# Sheet2.net
KiCad netlist of a schematic drawn in Altium Designer
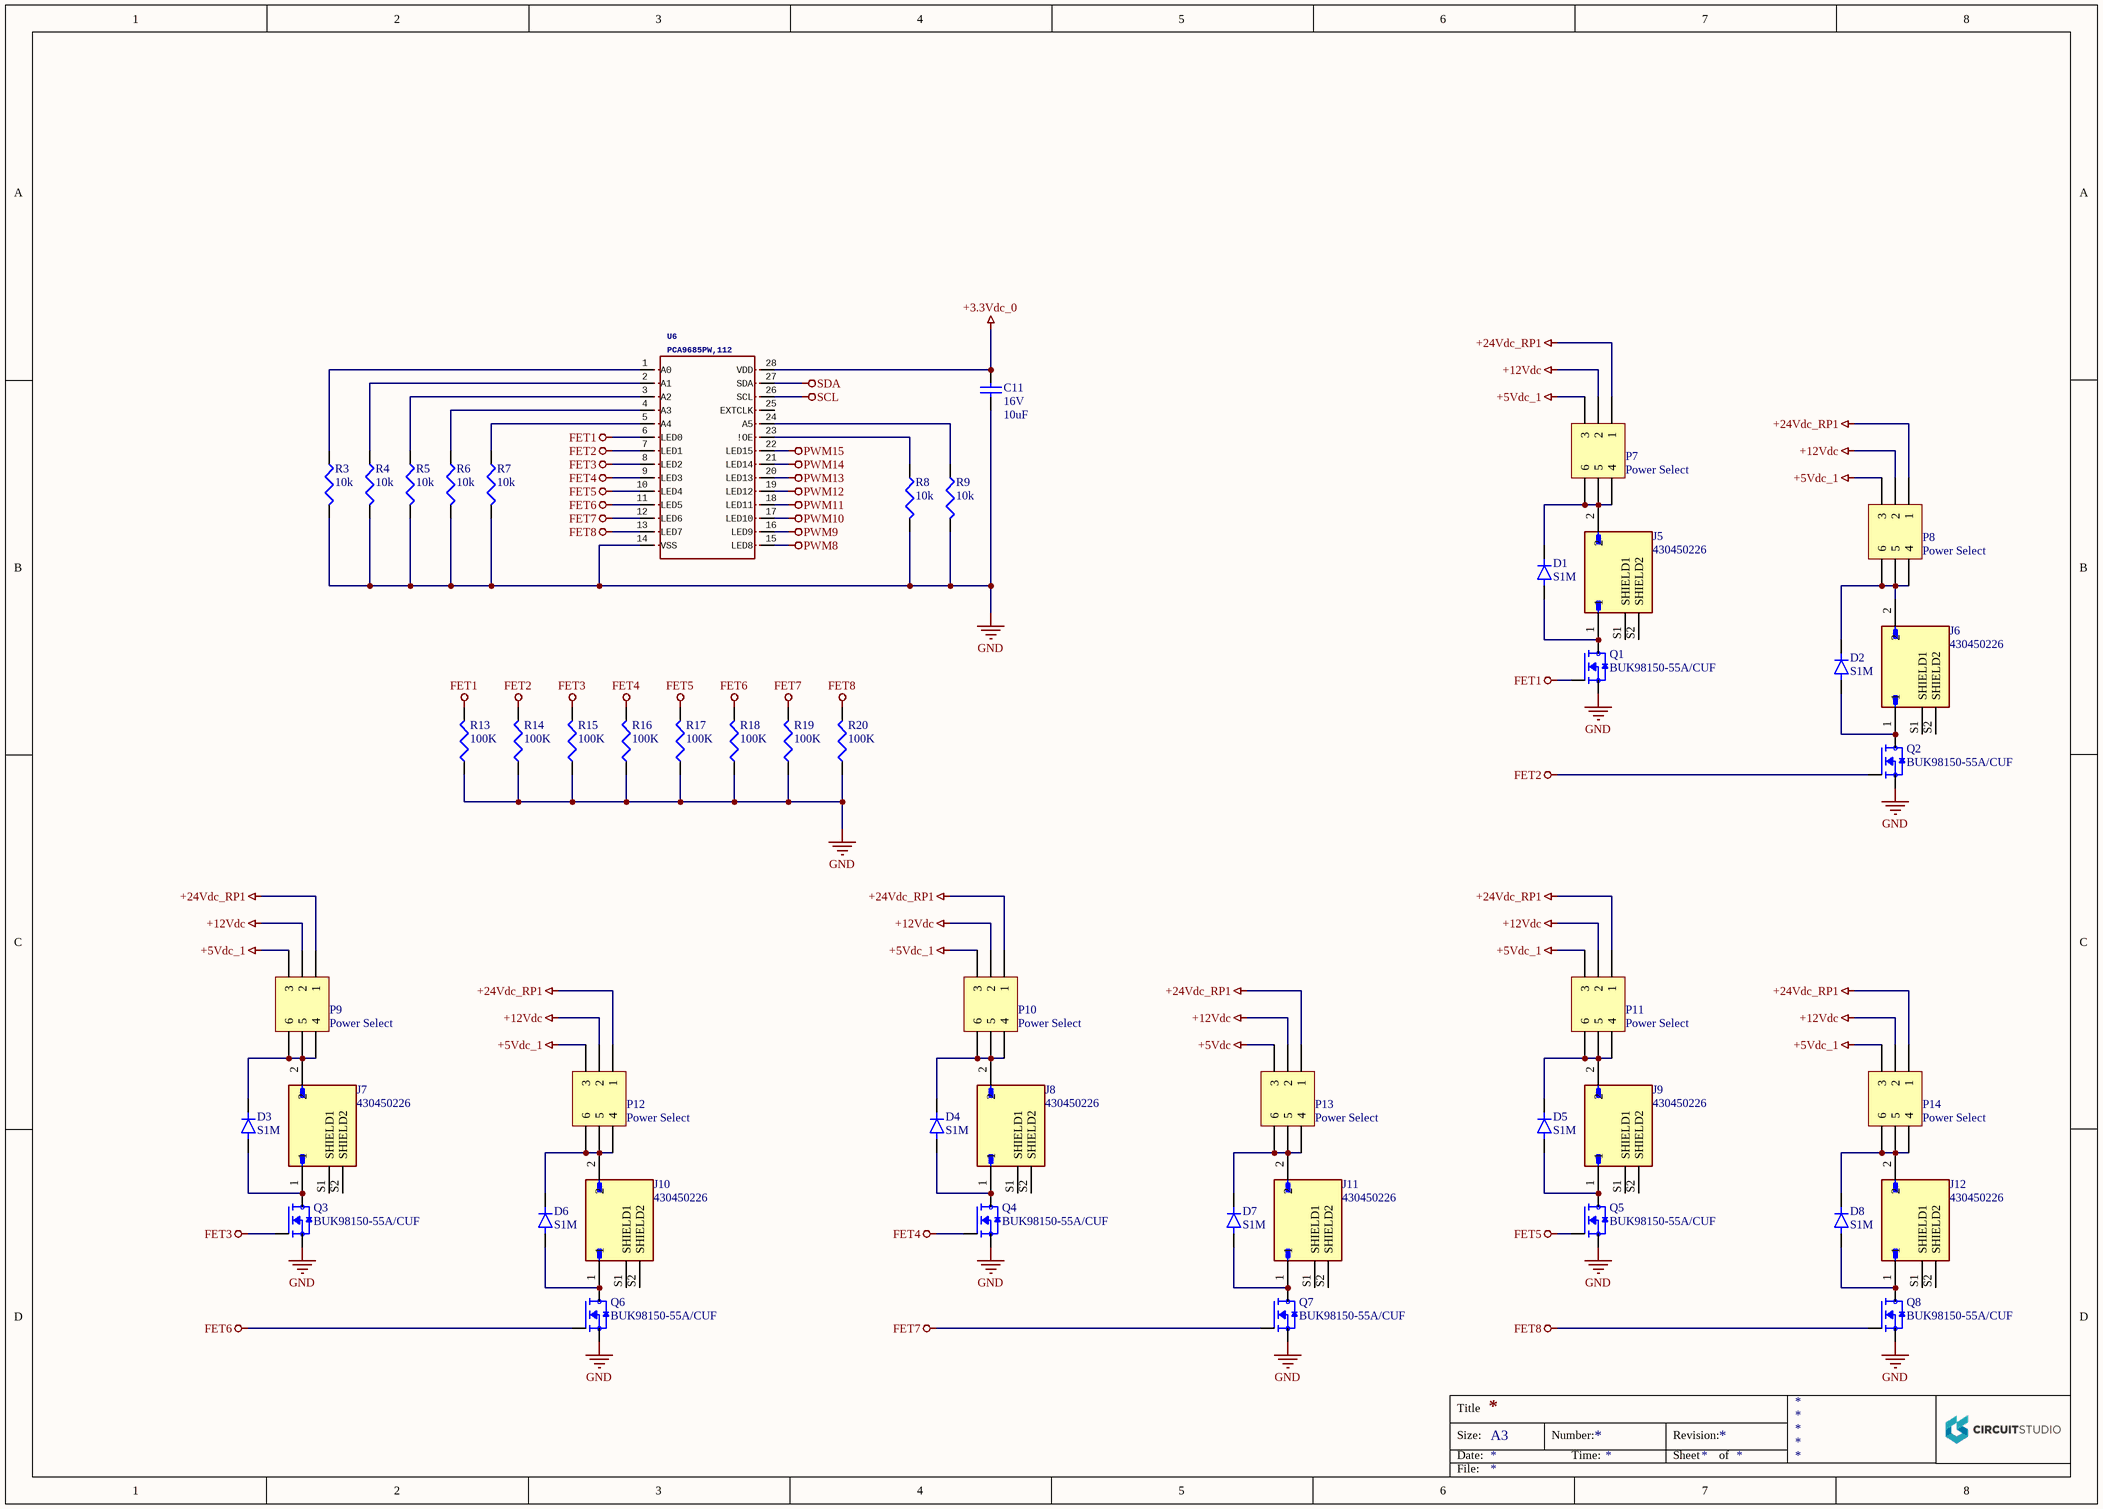
[diagram p0: Sheet2.SchDoc]

(export (version "E")
  (design (tool "Eeschema 10.0.6"))
  (components
    (comp (ref "C11")
      (value "16V")
      (footprint "1608[0603]")
      (description "CAP CER 10UF 16V X5R 0603")
      (fields
        (field (name "ALTIUM_VALUE") "10uF")
        (field (name "MANUFACTURER PART #") "CC0603KRX5R7BB106")
        (field (name "MANUFACTURER") "YAGEO")
      )
      (libsource (lib "Miscellaneous Devices") (part "Cap Semi"))
    )
    (comp (ref "D1")
      (value "S1M")
      (footprint "DIOM4325X250N")
      (description "DIODE GEN PURP 1KV 1A SMA")
      (fields
        (field (name "MANUFACTURER PART #") "S1MLHRVG")
        (field (name "MANUFACTURER") "Taiwan Semiconductor")
      )
      (libsource (lib "S1M") (part "S1M"))
    )
    (comp (ref "D2")
      (value "S1M")
      (footprint "DIOM4325X250N")
      (description "DIODE GEN PURP 1KV 1A SMA")
      (fields
        (field (name "MANUFACTURER PART #") "S1MLHRVG")
        (field (name "MANUFACTURER") "Taiwan Semiconductor")
      )
      (libsource (lib "S1M") (part "S1M"))
    )
    (comp (ref "D3")
      (value "S1M")
      (footprint "DIOM4325X250N")
      (description "DIODE GEN PURP 1KV 1A SMA")
      (fields
        (field (name "MANUFACTURER PART #") "S1MLHRVG")
        (field (name "MANUFACTURER") "Taiwan Semiconductor")
      )
      (libsource (lib "S1M") (part "S1M"))
    )
    (comp (ref "D4")
      (value "S1M")
      (footprint "DIOM4325X250N")
      (description "DIODE GEN PURP 1KV 1A SMA")
      (fields
        (field (name "MANUFACTURER PART #") "S1MLHRVG")
        (field (name "MANUFACTURER") "Taiwan Semiconductor")
      )
      (libsource (lib "S1M") (part "S1M"))
    )
    (comp (ref "D5")
      (value "S1M")
      (footprint "DIOM4325X250N")
      (description "DIODE GEN PURP 1KV 1A SMA")
      (fields
        (field (name "MANUFACTURER PART #") "S1MLHRVG")
        (field (name "MANUFACTURER") "Taiwan Semiconductor")
      )
      (libsource (lib "S1M") (part "S1M"))
    )
    (comp (ref "D6")
      (value "S1M")
      (footprint "DIOM4325X250N")
      (description "DIODE GEN PURP 1KV 1A SMA")
      (fields
        (field (name "MANUFACTURER PART #") "S1MLHRVG")
        (field (name "MANUFACTURER") "Taiwan Semiconductor")
      )
      (libsource (lib "S1M") (part "S1M"))
    )
    (comp (ref "D7")
      (value "S1M")
      (footprint "DIOM4325X250N")
      (description "DIODE GEN PURP 1KV 1A SMA")
      (fields
        (field (name "MANUFACTURER PART #") "S1MLHRVG")
        (field (name "MANUFACTURER") "Taiwan Semiconductor")
      )
      (libsource (lib "S1M") (part "S1M"))
    )
    (comp (ref "D8")
      (value "S1M")
      (footprint "DIOM4325X250N")
      (description "DIODE GEN PURP 1KV 1A SMA")
      (fields
        (field (name "MANUFACTURER PART #") "S1MLHRVG")
        (field (name "MANUFACTURER") "Taiwan Semiconductor")
      )
      (libsource (lib "S1M") (part "S1M"))
    )
    (comp (ref "J5")
      (value "430450226")
      (footprint "MOLEX_430450226")
      (description "CONN HEADER VERT 2POS")
      (fields (field (name "MANUFACTURER PART #") "0430450226"))
      (libsource (lib "2P_Vert_Microfit") (part "430450226"))
    )
    (comp (ref "J6")
      (value "430450226")
      (footprint "MOLEX_430450226")
      (description "CONN HEADER VERT 2POS")
      (fields (field (name "MANUFACTURER PART #") "0430450226"))
      (libsource (lib "2P_Vert_Microfit") (part "430450226"))
    )
    (comp (ref "J7")
      (value "430450226")
      (footprint "MOLEX_430450226")
      (description "CONN HEADER VERT 2POS")
      (fields (field (name "MANUFACTURER PART #") "0430450226"))
      (libsource (lib "2P_Vert_Microfit") (part "430450226"))
    )
    (comp (ref "J8")
      (value "430450226")
      (footprint "MOLEX_430450226")
      (description "CONN HEADER VERT 2POS")
      (fields (field (name "MANUFACTURER PART #") "0430450226"))
      (libsource (lib "2P_Vert_Microfit") (part "430450226"))
    )
    (comp (ref "J9")
      (value "430450226")
      (footprint "MOLEX_430450226")
      (description "CONN HEADER VERT 2POS")
      (fields (field (name "MANUFACTURER PART #") "0430450226"))
      (libsource (lib "2P_Vert_Microfit") (part "430450226"))
    )
    (comp (ref "J10")
      (value "430450226")
      (footprint "MOLEX_430450226")
      (description "CONN HEADER VERT 2POS")
      (fields (field (name "MANUFACTURER PART #") "0430450226"))
      (libsource (lib "2P_Vert_Microfit") (part "430450226"))
    )
    (comp (ref "J11")
      (value "430450226")
      (footprint "MOLEX_430450226")
      (description "CONN HEADER VERT 2POS")
      (fields (field (name "MANUFACTURER PART #") "0430450226"))
      (libsource (lib "2P_Vert_Microfit") (part "430450226"))
    )
    (comp (ref "J12")
      (value "430450226")
      (footprint "MOLEX_430450226")
      (description "CONN HEADER VERT 2POS")
      (fields (field (name "MANUFACTURER PART #") "0430450226"))
      (libsource (lib "2P_Vert_Microfit") (part "430450226"))
    )
    (comp (ref "P7")
      (value "Power Select")
      (footprint "HDR2X3_CEN")
      (description "Header, 3-Pin, Dual row")
      (fields
        (field (name "MANUFACTURER PART #") "67997-206HLF")
        (field (name "MANUFACTURER") "Amphenol ICC (FCI)")
      )
      (libsource (lib "Miscellaneous Connectors") (part "Header 3X2A"))
    )
    (comp (ref "P8")
      (value "Power Select")
      (footprint "HDR2X3_CEN")
      (description "Header, 3-Pin, Dual row")
      (fields
        (field (name "MANUFACTURER PART #") "67997-206HLF")
        (field (name "MANUFACTURER") "Amphenol ICC (FCI)")
      )
      (libsource (lib "Miscellaneous Connectors") (part "Header 3X2A"))
    )
    (comp (ref "P9")
      (value "Power Select")
      (footprint "HDR2X3_CEN")
      (description "Header, 3-Pin, Dual row")
      (fields
        (field (name "MANUFACTURER PART #") "67997-206HLF")
        (field (name "MANUFACTURER") "Amphenol ICC (FCI)")
      )
      (libsource (lib "Miscellaneous Connectors") (part "Header 3X2A"))
    )
    (comp (ref "P10")
      (value "Power Select")
      (footprint "HDR2X3_CEN")
      (description "Header, 3-Pin, Dual row")
      (fields
        (field (name "MANUFACTURER PART #") "67997-206HLF")
        (field (name "MANUFACTURER") "Amphenol ICC (FCI)")
      )
      (libsource (lib "Miscellaneous Connectors") (part "Header 3X2A"))
    )
    (comp (ref "P11")
      (value "Power Select")
      (footprint "HDR2X3_CEN")
      (description "Header, 3-Pin, Dual row")
      (fields
        (field (name "MANUFACTURER PART #") "67997-206HLF")
        (field (name "MANUFACTURER") "Amphenol ICC (FCI)")
      )
      (libsource (lib "Miscellaneous Connectors") (part "Header 3X2A"))
    )
    (comp (ref "P12")
      (value "Power Select")
      (footprint "HDR2X3_CEN")
      (description "Header, 3-Pin, Dual row")
      (fields
        (field (name "MANUFACTURER PART #") "67997-206HLF")
        (field (name "MANUFACTURER") "Amphenol ICC (FCI)")
      )
      (libsource (lib "Miscellaneous Connectors") (part "Header 3X2A"))
    )
    (comp (ref "P13")
      (value "Power Select")
      (footprint "HDR2X3_CEN")
      (description "Header, 3-Pin, Dual row")
      (fields
        (field (name "MANUFACTURER PART #") "67997-206HLF")
        (field (name "MANUFACTURER") "Amphenol ICC (FCI)")
      )
      (libsource (lib "Miscellaneous Connectors") (part "Header 3X2A"))
    )
    (comp (ref "P14")
      (value "Power Select")
      (footprint "HDR2X3_CEN")
      (description "Header, 3-Pin, Dual row")
      (fields
        (field (name "MANUFACTURER PART #") "67997-206HLF")
        (field (name "MANUFACTURER") "Amphenol ICC (FCI)")
      )
      (libsource (lib "Miscellaneous Connectors") (part "Header 3X2A"))
    )
    (comp (ref "Q1")
      (value "BUK98150-55A/CUF")
      (footprint "SOT230P700X180-4N")
      (description "N-MOSFET N-CH 55V 5.5A SOT223")
      (fields (field (name "MANUFACTURER") "Nexperia USA"))
      (libsource (lib "BUK98150-55A_CUF") (part "BUK98150-55A/CUF"))
    )
    (comp (ref "Q2")
      (value "BUK98150-55A/CUF")
      (footprint "SOT230P700X180-4N")
      (description "N-MOSFET N-CH 55V 5.5A SOT223")
      (fields (field (name "MANUFACTURER") "Nexperia USA"))
      (libsource (lib "BUK98150-55A_CUF") (part "BUK98150-55A/CUF"))
    )
    (comp (ref "Q3")
      (value "BUK98150-55A/CUF")
      (footprint "SOT230P700X180-4N")
      (description "N-MOSFET N-CH 55V 5.5A SOT223")
      (fields (field (name "MANUFACTURER") "Nexperia USA"))
      (libsource (lib "BUK98150-55A_CUF") (part "BUK98150-55A/CUF"))
    )
    (comp (ref "Q4")
      (value "BUK98150-55A/CUF")
      (footprint "SOT230P700X180-4N")
      (description "N-MOSFET N-CH 55V 5.5A SOT223")
      (fields (field (name "MANUFACTURER") "Nexperia USA"))
      (libsource (lib "BUK98150-55A_CUF") (part "BUK98150-55A/CUF"))
    )
    (comp (ref "Q5")
      (value "BUK98150-55A/CUF")
      (footprint "SOT230P700X180-4N")
      (description "N-MOSFET N-CH 55V 5.5A SOT223")
      (fields (field (name "MANUFACTURER") "Nexperia USA"))
      (libsource (lib "BUK98150-55A_CUF") (part "BUK98150-55A/CUF"))
    )
    (comp (ref "Q6")
      (value "BUK98150-55A/CUF")
      (footprint "SOT230P700X180-4N")
      (description "N-MOSFET N-CH 55V 5.5A SOT223")
      (fields (field (name "MANUFACTURER") "Nexperia USA"))
      (libsource (lib "BUK98150-55A_CUF") (part "BUK98150-55A/CUF"))
    )
    (comp (ref "Q7")
      (value "BUK98150-55A/CUF")
      (footprint "SOT230P700X180-4N")
      (description "N-MOSFET N-CH 55V 5.5A SOT223")
      (fields (field (name "MANUFACTURER") "Nexperia USA"))
      (libsource (lib "BUK98150-55A_CUF") (part "BUK98150-55A/CUF"))
    )
    (comp (ref "Q8")
      (value "BUK98150-55A/CUF")
      (footprint "SOT230P700X180-4N")
      (description "N-MOSFET N-CH 55V 5.5A SOT223")
      (fields (field (name "MANUFACTURER") "Nexperia USA"))
      (libsource (lib "BUK98150-55A_CUF") (part "BUK98150-55A/CUF"))
    )
    (comp (ref "R3")
      (value "10k")
      (footprint "0402")
      (description "RES 10 KOHM 1% 1/8W 0402")
      (fields (field (name "MANUFACTURER PART #") "AC0402FR-7W10KL") (field (name "MANUFACTURER") "YAGEO"))
      (libsource (lib "Miscellaneous Devices") (part "Res3"))
    )
    (comp (ref "R4")
      (value "10k")
      (footprint "0402")
      (description "RES 10 KOHM 1% 1/8W 0402")
      (fields (field (name "MANUFACTURER PART #") "AC0402FR-7W10KL") (field (name "MANUFACTURER") "YAGEO"))
      (libsource (lib "Miscellaneous Devices") (part "Res3"))
    )
    (comp (ref "R5")
      (value "10k")
      (footprint "0402")
      (description "RES 10 KOHM 1% 1/8W 0402")
      (fields (field (name "MANUFACTURER PART #") "AC0402FR-7W10KL") (field (name "MANUFACTURER") "YAGEO"))
      (libsource (lib "Miscellaneous Devices") (part "Res3"))
    )
    (comp (ref "R6")
      (value "10k")
      (footprint "0402")
      (description "RES 10 KOHM 1% 1/8W 0402")
      (fields (field (name "MANUFACTURER PART #") "AC0402FR-7W10KL") (field (name "MANUFACTURER") "YAGEO"))
      (libsource (lib "Miscellaneous Devices") (part "Res3"))
    )
    (comp (ref "R7")
      (value "10k")
      (footprint "0402")
      (description "RES 10 KOHM 1% 1/8W 0402")
      (fields (field (name "MANUFACTURER PART #") "AC0402FR-7W10KL") (field (name "MANUFACTURER") "YAGEO"))
      (libsource (lib "Miscellaneous Devices") (part "Res3"))
    )
    (comp (ref "R8")
      (value "10k")
      (footprint "0402")
      (description "RES 10 KOHM 1% 1/8W 0402")
      (fields (field (name "MANUFACTURER PART #") "AC0402FR-7W10KL") (field (name "MANUFACTURER") "YAGEO"))
      (libsource (lib "Miscellaneous Devices") (part "Res3"))
    )
    (comp (ref "R9")
      (value "10k")
      (footprint "0402")
      (description "RES 10 KOHM 1% 1/8W 0402")
      (fields (field (name "MANUFACTURER PART #") "AC0402FR-7W10KL") (field (name "MANUFACTURER") "YAGEO"))
      (libsource (lib "Miscellaneous Devices") (part "Res3"))
    )
    (comp (ref "R13")
      (value "100K")
      (footprint "J1-0603")
      (description "RES 100K OHM 1% 1/4W 0603")
      (fields (field (name "MANUFACTURER PART #") "SR0603FR-7T100KL") (field (name "MANUFACTURER") "YAGEO"))
      (libsource (lib "Miscellaneous Devices") (part "Res3"))
    )
    (comp (ref "R14")
      (value "100K")
      (footprint "J1-0603")
      (description "RES 100K OHM 1% 1/4W 0603")
      (fields (field (name "MANUFACTURER PART #") "SR0603FR-7T100KL") (field (name "MANUFACTURER") "YAGEO"))
      (libsource (lib "Miscellaneous Devices") (part "Res3"))
    )
    (comp (ref "R15")
      (value "100K")
      (footprint "J1-0603")
      (description "RES 100K OHM 1% 1/4W 0603")
      (fields (field (name "MANUFACTURER PART #") "SR0603FR-7T100KL") (field (name "MANUFACTURER") "YAGEO"))
      (libsource (lib "Miscellaneous Devices") (part "Res3"))
    )
    (comp (ref "R16")
      (value "100K")
      (footprint "J1-0603")
      (description "RES 100K OHM 1% 1/4W 0603")
      (fields (field (name "MANUFACTURER PART #") "SR0603FR-7T100KL") (field (name "MANUFACTURER") "YAGEO"))
      (libsource (lib "Miscellaneous Devices") (part "Res3"))
    )
    (comp (ref "R17")
      (value "100K")
      (footprint "J1-0603")
      (description "RES 100K OHM 1% 1/4W 0603")
      (fields (field (name "MANUFACTURER PART #") "SR0603FR-7T100KL") (field (name "MANUFACTURER") "YAGEO"))
      (libsource (lib "Miscellaneous Devices") (part "Res3"))
    )
    (comp (ref "R18")
      (value "100K")
      (footprint "J1-0603")
      (description "RES 100K OHM 1% 1/4W 0603")
      (fields (field (name "MANUFACTURER PART #") "SR0603FR-7T100KL") (field (name "MANUFACTURER") "YAGEO"))
      (libsource (lib "Miscellaneous Devices") (part "Res3"))
    )
    (comp (ref "R19")
      (value "100K")
      (footprint "J1-0603")
      (description "RES 100K OHM 1% 1/4W 0603")
      (fields (field (name "MANUFACTURER PART #") "SR0603FR-7T100KL") (field (name "MANUFACTURER") "YAGEO"))
      (libsource (lib "Miscellaneous Devices") (part "Res3"))
    )
    (comp (ref "R20")
      (value "100K")
      (footprint "J1-0603")
      (description "RES 100K OHM 1% 1/4W 0603")
      (fields (field (name "MANUFACTURER PART #") "SR0603FR-7T100KL") (field (name "MANUFACTURER") "YAGEO"))
      (libsource (lib "Miscellaneous Devices") (part "Res3"))
    )
    (comp (ref "U6")
      (value "PCA9685PW,112")
      (footprint "TSSOP28-0.65-9.7X4.4MM")
      (fields (field (name "MANUFACTURER") "NXP USA"))
      (libsource (lib "PCA9685PW") (part "DRIVER-PCA9685PW(TSSOP28)"))
    )
  )
  (nets
    (net (code "1") (name "+3.3Vdc_0") (class "Default")
      (node (ref "C11") (pin "1") (pinfunction "1_1") (pintype "passive"))
      (node (ref "U6") (pin "28") (pinfunction "VDD_28") (pintype "passive"))
    )
    (net (code "2") (name "+5Vdc") (class "Default")
      (node (ref "P13") (pin "3") (pinfunction "3_3") (pintype "passive"))
    )
    (net (code "3") (name "+5Vdc_1") (class "Default")
      (node (ref "P10") (pin "3") (pinfunction "3_3") (pintype "passive"))
      (node (ref "P11") (pin "3") (pinfunction "3_3") (pintype "passive"))
      (node (ref "P12") (pin "3") (pinfunction "3_3") (pintype "passive"))
      (node (ref "P14") (pin "3") (pinfunction "3_3") (pintype "passive"))
      (node (ref "P7") (pin "3") (pinfunction "3_3") (pintype "passive"))
      (node (ref "P8") (pin "3") (pinfunction "3_3") (pintype "passive"))
      (node (ref "P9") (pin "3") (pinfunction "3_3") (pintype "passive"))
    )
    (net (code "4") (name "+12Vdc") (class "Default")
      (node (ref "P10") (pin "2") (pinfunction "2_2") (pintype "passive"))
      (node (ref "P11") (pin "2") (pinfunction "2_2") (pintype "passive"))
      (node (ref "P12") (pin "2") (pinfunction "2_2") (pintype "passive"))
      (node (ref "P13") (pin "2") (pinfunction "2_2") (pintype "passive"))
      (node (ref "P14") (pin "2") (pinfunction "2_2") (pintype "passive"))
      (node (ref "P7") (pin "2") (pinfunction "2_2") (pintype "passive"))
      (node (ref "P8") (pin "2") (pinfunction "2_2") (pintype "passive"))
      (node (ref "P9") (pin "2") (pinfunction "2_2") (pintype "passive"))
    )
    (net (code "5") (name "+24Vdc_RP1") (class "Default")
      (node (ref "P10") (pin "1") (pinfunction "1_1") (pintype "passive"))
      (node (ref "P11") (pin "1") (pinfunction "1_1") (pintype "passive"))
      (node (ref "P12") (pin "1") (pinfunction "1_1") (pintype "passive"))
      (node (ref "P13") (pin "1") (pinfunction "1_1") (pintype "passive"))
      (node (ref "P14") (pin "1") (pinfunction "1_1") (pintype "passive"))
      (node (ref "P7") (pin "1") (pinfunction "1_1") (pintype "passive"))
      (node (ref "P8") (pin "1") (pinfunction "1_1") (pintype "passive"))
      (node (ref "P9") (pin "1") (pinfunction "1_1") (pintype "passive"))
    )
    (net (code "6") (name "FET1") (class "Default")
      (node (ref "Q1") (pin "1") (pinfunction "G_1") (pintype "passive"))
      (node (ref "R13") (pin "2") (pinfunction "2_2") (pintype "passive"))
      (node (ref "U6") (pin "6") (pinfunction "LED0_6") (pintype "passive"))
    )
    (net (code "7") (name "FET2") (class "Default")
      (node (ref "Q2") (pin "1") (pinfunction "G_1") (pintype "passive"))
      (node (ref "R14") (pin "2") (pinfunction "2_2") (pintype "passive"))
      (node (ref "U6") (pin "7") (pinfunction "LED1_7") (pintype "passive"))
    )
    (net (code "8") (name "FET3") (class "Default")
      (node (ref "Q3") (pin "1") (pinfunction "G_1") (pintype "passive"))
      (node (ref "R15") (pin "2") (pinfunction "2_2") (pintype "passive"))
      (node (ref "U6") (pin "8") (pinfunction "LED2_8") (pintype "passive"))
    )
    (net (code "9") (name "FET4") (class "Default")
      (node (ref "Q4") (pin "1") (pinfunction "G_1") (pintype "passive"))
      (node (ref "R16") (pin "2") (pinfunction "2_2") (pintype "passive"))
      (node (ref "U6") (pin "9") (pinfunction "LED3_9") (pintype "passive"))
    )
    (net (code "10") (name "FET5") (class "Default")
      (node (ref "Q5") (pin "1") (pinfunction "G_1") (pintype "passive"))
      (node (ref "R17") (pin "2") (pinfunction "2_2") (pintype "passive"))
      (node (ref "U6") (pin "10") (pinfunction "LED4_10") (pintype "passive"))
    )
    (net (code "11") (name "FET6") (class "Default")
      (node (ref "Q6") (pin "1") (pinfunction "G_1") (pintype "passive"))
      (node (ref "R18") (pin "2") (pinfunction "2_2") (pintype "passive"))
      (node (ref "U6") (pin "11") (pinfunction "LED5_11") (pintype "passive"))
    )
    (net (code "12") (name "FET7") (class "Default")
      (node (ref "Q7") (pin "1") (pinfunction "G_1") (pintype "passive"))
      (node (ref "R19") (pin "2") (pinfunction "2_2") (pintype "passive"))
      (node (ref "U6") (pin "12") (pinfunction "LED6_12") (pintype "passive"))
    )
    (net (code "13") (name "FET8") (class "Default")
      (node (ref "Q8") (pin "1") (pinfunction "G_1") (pintype "passive"))
      (node (ref "R20") (pin "2") (pinfunction "2_2") (pintype "passive"))
      (node (ref "U6") (pin "13") (pinfunction "LED7_13") (pintype "passive"))
    )
    (net (code "14") (name "GND") (class "Default")
      (node (ref "C11") (pin "2") (pinfunction "2_2") (pintype "passive"))
      (node (ref "Q1") (pin "3") (pinfunction "S_3") (pintype "passive"))
      (node (ref "Q2") (pin "3") (pinfunction "S_3") (pintype "passive"))
      (node (ref "Q3") (pin "3") (pinfunction "S_3") (pintype "passive"))
      (node (ref "Q4") (pin "3") (pinfunction "S_3") (pintype "passive"))
      (node (ref "Q5") (pin "3") (pinfunction "S_3") (pintype "passive"))
      (node (ref "Q6") (pin "3") (pinfunction "S_3") (pintype "passive"))
      (node (ref "Q7") (pin "3") (pinfunction "S_3") (pintype "passive"))
      (node (ref "Q8") (pin "3") (pinfunction "S_3") (pintype "passive"))
      (node (ref "R13") (pin "1") (pinfunction "1_1") (pintype "passive"))
      (node (ref "R14") (pin "1") (pinfunction "1_1") (pintype "passive"))
      (node (ref "R15") (pin "1") (pinfunction "1_1") (pintype "passive"))
      (node (ref "R16") (pin "1") (pinfunction "1_1") (pintype "passive"))
      (node (ref "R17") (pin "1") (pinfunction "1_1") (pintype "passive"))
      (node (ref "R18") (pin "1") (pinfunction "1_1") (pintype "passive"))
      (node (ref "R19") (pin "1") (pinfunction "1_1") (pintype "passive"))
      (node (ref "R20") (pin "1") (pinfunction "1_1") (pintype "passive"))
      (node (ref "R3") (pin "2") (pinfunction "2_2") (pintype "passive"))
      (node (ref "R4") (pin "2") (pinfunction "2_2") (pintype "passive"))
      (node (ref "R5") (pin "2") (pinfunction "2_2") (pintype "passive"))
      (node (ref "R6") (pin "2") (pinfunction "2_2") (pintype "passive"))
      (node (ref "R7") (pin "2") (pinfunction "2_2") (pintype "passive"))
      (node (ref "R8") (pin "2") (pinfunction "2_2") (pintype "passive"))
      (node (ref "R9") (pin "2") (pinfunction "2_2") (pintype "passive"))
      (node (ref "U6") (pin "14") (pinfunction "VSS_14") (pintype "passive"))
    )
    (net (code "15") (name "Net-(D1-K)") (class "Default")
      (node (ref "D1") (pin "C") (pinfunction "K_C") (pintype "passive"))
      (node (ref "J5") (pin "2") (pinfunction "2_2") (pintype "passive"))
      (node (ref "P7") (pin "4") (pinfunction "4_4") (pintype "passive"))
      (node (ref "P7") (pin "5") (pinfunction "5_5") (pintype "passive"))
      (node (ref "P7") (pin "6") (pinfunction "6_6") (pintype "passive"))
    )
    (net (code "16") (name "Net-(D1-PadA)") (class "Default")
      (node (ref "D1") (pin "A") (pinfunction "A_A") (pintype "passive"))
      (node (ref "J5") (pin "1") (pinfunction "1_1") (pintype "passive"))
      (node (ref "Q1") (pin "2") (pinfunction "D_2") (pintype "passive"))
      (node (ref "Q1") (pin "4") (pinfunction "D_4") (pintype "passive"))
    )
    (net (code "17") (name "Net-(D2-K)") (class "Default")
      (node (ref "D2") (pin "C") (pinfunction "K_C") (pintype "passive"))
      (node (ref "J6") (pin "2") (pinfunction "2_2") (pintype "passive"))
      (node (ref "P8") (pin "4") (pinfunction "4_4") (pintype "passive"))
      (node (ref "P8") (pin "5") (pinfunction "5_5") (pintype "passive"))
      (node (ref "P8") (pin "6") (pinfunction "6_6") (pintype "passive"))
    )
    (net (code "18") (name "Net-(D2-PadA)") (class "Default")
      (node (ref "D2") (pin "A") (pinfunction "A_A") (pintype "passive"))
      (node (ref "J6") (pin "1") (pinfunction "1_1") (pintype "passive"))
      (node (ref "Q2") (pin "2") (pinfunction "D_2") (pintype "passive"))
      (node (ref "Q2") (pin "4") (pinfunction "D_4") (pintype "passive"))
    )
    (net (code "19") (name "Net-(D3-K)") (class "Default")
      (node (ref "D3") (pin "C") (pinfunction "K_C") (pintype "passive"))
      (node (ref "J7") (pin "2") (pinfunction "2_2") (pintype "passive"))
      (node (ref "P9") (pin "4") (pinfunction "4_4") (pintype "passive"))
      (node (ref "P9") (pin "5") (pinfunction "5_5") (pintype "passive"))
      (node (ref "P9") (pin "6") (pinfunction "6_6") (pintype "passive"))
    )
    (net (code "20") (name "Net-(D3-PadA)") (class "Default")
      (node (ref "D3") (pin "A") (pinfunction "A_A") (pintype "passive"))
      (node (ref "J7") (pin "1") (pinfunction "1_1") (pintype "passive"))
      (node (ref "Q3") (pin "2") (pinfunction "D_2") (pintype "passive"))
      (node (ref "Q3") (pin "4") (pinfunction "D_4") (pintype "passive"))
    )
    (net (code "21") (name "Net-(D4-K)") (class "Default")
      (node (ref "D4") (pin "C") (pinfunction "K_C") (pintype "passive"))
      (node (ref "J8") (pin "2") (pinfunction "2_2") (pintype "passive"))
      (node (ref "P10") (pin "4") (pinfunction "4_4") (pintype "passive"))
      (node (ref "P10") (pin "5") (pinfunction "5_5") (pintype "passive"))
      (node (ref "P10") (pin "6") (pinfunction "6_6") (pintype "passive"))
    )
    (net (code "22") (name "Net-(D4-PadA)") (class "Default")
      (node (ref "D4") (pin "A") (pinfunction "A_A") (pintype "passive"))
      (node (ref "J8") (pin "1") (pinfunction "1_1") (pintype "passive"))
      (node (ref "Q4") (pin "2") (pinfunction "D_2") (pintype "passive"))
      (node (ref "Q4") (pin "4") (pinfunction "D_4") (pintype "passive"))
    )
    (net (code "23") (name "Net-(D5-K)") (class "Default")
      (node (ref "D5") (pin "C") (pinfunction "K_C") (pintype "passive"))
      (node (ref "J9") (pin "2") (pinfunction "2_2") (pintype "passive"))
      (node (ref "P11") (pin "4") (pinfunction "4_4") (pintype "passive"))
      (node (ref "P11") (pin "5") (pinfunction "5_5") (pintype "passive"))
      (node (ref "P11") (pin "6") (pinfunction "6_6") (pintype "passive"))
    )
    (net (code "24") (name "Net-(D5-PadA)") (class "Default")
      (node (ref "D5") (pin "A") (pinfunction "A_A") (pintype "passive"))
      (node (ref "J9") (pin "1") (pinfunction "1_1") (pintype "passive"))
      (node (ref "Q5") (pin "2") (pinfunction "D_2") (pintype "passive"))
      (node (ref "Q5") (pin "4") (pinfunction "D_4") (pintype "passive"))
    )
    (net (code "25") (name "Net-(D6-K)") (class "Default")
      (node (ref "D6") (pin "C") (pinfunction "K_C") (pintype "passive"))
      (node (ref "J10") (pin "2") (pinfunction "2_2") (pintype "passive"))
      (node (ref "P12") (pin "4") (pinfunction "4_4") (pintype "passive"))
      (node (ref "P12") (pin "5") (pinfunction "5_5") (pintype "passive"))
      (node (ref "P12") (pin "6") (pinfunction "6_6") (pintype "passive"))
    )
    (net (code "26") (name "Net-(D6-PadA)") (class "Default")
      (node (ref "D6") (pin "A") (pinfunction "A_A") (pintype "passive"))
      (node (ref "J10") (pin "1") (pinfunction "1_1") (pintype "passive"))
      (node (ref "Q6") (pin "2") (pinfunction "D_2") (pintype "passive"))
      (node (ref "Q6") (pin "4") (pinfunction "D_4") (pintype "passive"))
    )
    (net (code "27") (name "Net-(D7-K)") (class "Default")
      (node (ref "D7") (pin "C") (pinfunction "K_C") (pintype "passive"))
      (node (ref "J11") (pin "2") (pinfunction "2_2") (pintype "passive"))
      (node (ref "P13") (pin "4") (pinfunction "4_4") (pintype "passive"))
      (node (ref "P13") (pin "5") (pinfunction "5_5") (pintype "passive"))
      (node (ref "P13") (pin "6") (pinfunction "6_6") (pintype "passive"))
    )
    (net (code "28") (name "Net-(D7-PadA)") (class "Default")
      (node (ref "D7") (pin "A") (pinfunction "A_A") (pintype "passive"))
      (node (ref "J11") (pin "1") (pinfunction "1_1") (pintype "passive"))
      (node (ref "Q7") (pin "2") (pinfunction "D_2") (pintype "passive"))
      (node (ref "Q7") (pin "4") (pinfunction "D_4") (pintype "passive"))
    )
    (net (code "29") (name "Net-(D8-K)") (class "Default")
      (node (ref "D8") (pin "C") (pinfunction "K_C") (pintype "passive"))
      (node (ref "J12") (pin "2") (pinfunction "2_2") (pintype "passive"))
      (node (ref "P14") (pin "4") (pinfunction "4_4") (pintype "passive"))
      (node (ref "P14") (pin "5") (pinfunction "5_5") (pintype "passive"))
      (node (ref "P14") (pin "6") (pinfunction "6_6") (pintype "passive"))
    )
    (net (code "30") (name "Net-(D8-PadA)") (class "Default")
      (node (ref "D8") (pin "A") (pinfunction "A_A") (pintype "passive"))
      (node (ref "J12") (pin "1") (pinfunction "1_1") (pintype "passive"))
      (node (ref "Q8") (pin "2") (pinfunction "D_2") (pintype "passive"))
      (node (ref "Q8") (pin "4") (pinfunction "D_4") (pintype "passive"))
    )
    (net (code "31") (name "Net-(U6-!OE)") (class "Default")
      (node (ref "R8") (pin "1") (pinfunction "1_1") (pintype "passive"))
      (node (ref "U6") (pin "23") (pinfunction "!OE_23") (pintype "passive"))
    )
    (net (code "32") (name "Net-(U6-A0)") (class "Default")
      (node (ref "R3") (pin "1") (pinfunction "1_1") (pintype "passive"))
      (node (ref "U6") (pin "1") (pinfunction "A0_1") (pintype "passive"))
    )
    (net (code "33") (name "Net-(U6-A1)") (class "Default")
      (node (ref "R4") (pin "1") (pinfunction "1_1") (pintype "passive"))
      (node (ref "U6") (pin "2") (pinfunction "A1_2") (pintype "passive"))
    )
    (net (code "34") (name "Net-(U6-A2)") (class "Default")
      (node (ref "R5") (pin "1") (pinfunction "1_1") (pintype "passive"))
      (node (ref "U6") (pin "3") (pinfunction "A2_3") (pintype "passive"))
    )
    (net (code "35") (name "Net-(U6-A3)") (class "Default")
      (node (ref "R6") (pin "1") (pinfunction "1_1") (pintype "passive"))
      (node (ref "U6") (pin "4") (pinfunction "A3_4") (pintype "passive"))
    )
    (net (code "36") (name "Net-(U6-A4)") (class "Default")
      (node (ref "R7") (pin "1") (pinfunction "1_1") (pintype "passive"))
      (node (ref "U6") (pin "5") (pinfunction "A4_5") (pintype "passive"))
    )
    (net (code "37") (name "Net-(U6-A5)") (class "Default")
      (node (ref "R9") (pin "1") (pinfunction "1_1") (pintype "passive"))
      (node (ref "U6") (pin "24") (pinfunction "A5_24") (pintype "passive"))
    )
    (net (code "38") (name "PWM8") (class "Default")
      (node (ref "U6") (pin "15") (pinfunction "LED8_15") (pintype "passive"))
    )
    (net (code "39") (name "PWM9") (class "Default")
      (node (ref "U6") (pin "16") (pinfunction "LED9_16") (pintype "passive"))
    )
    (net (code "40") (name "PWM10") (class "Default")
      (node (ref "U6") (pin "17") (pinfunction "LED10_17") (pintype "passive"))
    )
    (net (code "41") (name "PWM11") (class "Default")
      (node (ref "U6") (pin "18") (pinfunction "LED11_18") (pintype "passive"))
    )
    (net (code "42") (name "PWM12") (class "Default")
      (node (ref "U6") (pin "19") (pinfunction "LED12_19") (pintype "passive"))
    )
    (net (code "43") (name "PWM13") (class "Default")
      (node (ref "U6") (pin "20") (pinfunction "LED13_20") (pintype "passive"))
    )
    (net (code "44") (name "PWM14") (class "Default")
      (node (ref "U6") (pin "21") (pinfunction "LED14_21") (pintype "passive"))
    )
    (net (code "45") (name "PWM15") (class "Default")
      (node (ref "U6") (pin "22") (pinfunction "LED15_22") (pintype "passive"))
    )
    (net (code "46") (name "SCL") (class "Default")
      (node (ref "U6") (pin "26") (pinfunction "SCL_26") (pintype "passive"))
    )
    (net (code "47") (name "SDA") (class "Default")
      (node (ref "U6") (pin "27") (pinfunction "SDA_27") (pintype "passive"))
    )
    (net (code "48") (name "unconnected-(J5-SHIELD1-PadS1)") (class "Default")
      (node (ref "J5") (pin "S1") (pinfunction "SHIELD1_S1") (pintype "passive"))
    )
    (net (code "49") (name "unconnected-(J5-SHIELD2-PadS2)") (class "Default")
      (node (ref "J5") (pin "S2") (pinfunction "SHIELD2_S2") (pintype "passive"))
    )
    (net (code "50") (name "unconnected-(J6-SHIELD1-PadS1)") (class "Default")
      (node (ref "J6") (pin "S1") (pinfunction "SHIELD1_S1") (pintype "passive"))
    )
    (net (code "51") (name "unconnected-(J6-SHIELD2-PadS2)") (class "Default")
      (node (ref "J6") (pin "S2") (pinfunction "SHIELD2_S2") (pintype "passive"))
    )
    (net (code "52") (name "unconnected-(J7-SHIELD1-PadS1)") (class "Default")
      (node (ref "J7") (pin "S1") (pinfunction "SHIELD1_S1") (pintype "passive"))
    )
    (net (code "53") (name "unconnected-(J7-SHIELD2-PadS2)") (class "Default")
      (node (ref "J7") (pin "S2") (pinfunction "SHIELD2_S2") (pintype "passive"))
    )
    (net (code "54") (name "unconnected-(J8-SHIELD1-PadS1)") (class "Default")
      (node (ref "J8") (pin "S1") (pinfunction "SHIELD1_S1") (pintype "passive"))
    )
    (net (code "55") (name "unconnected-(J8-SHIELD2-PadS2)") (class "Default")
      (node (ref "J8") (pin "S2") (pinfunction "SHIELD2_S2") (pintype "passive"))
    )
    (net (code "56") (name "unconnected-(J9-SHIELD1-PadS1)") (class "Default")
      (node (ref "J9") (pin "S1") (pinfunction "SHIELD1_S1") (pintype "passive"))
    )
    (net (code "57") (name "unconnected-(J9-SHIELD2-PadS2)") (class "Default")
      (node (ref "J9") (pin "S2") (pinfunction "SHIELD2_S2") (pintype "passive"))
    )
    (net (code "58") (name "unconnected-(J10-SHIELD1-PadS1)") (class "Default")
      (node (ref "J10") (pin "S1") (pinfunction "SHIELD1_S1") (pintype "passive"))
    )
    (net (code "59") (name "unconnected-(J10-SHIELD2-PadS2)") (class "Default")
      (node (ref "J10") (pin "S2") (pinfunction "SHIELD2_S2") (pintype "passive"))
    )
    (net (code "60") (name "unconnected-(J11-SHIELD1-PadS1)") (class "Default")
      (node (ref "J11") (pin "S1") (pinfunction "SHIELD1_S1") (pintype "passive"))
    )
    (net (code "61") (name "unconnected-(J11-SHIELD2-PadS2)") (class "Default")
      (node (ref "J11") (pin "S2") (pinfunction "SHIELD2_S2") (pintype "passive"))
    )
    (net (code "62") (name "unconnected-(J12-SHIELD1-PadS1)") (class "Default")
      (node (ref "J12") (pin "S1") (pinfunction "SHIELD1_S1") (pintype "passive"))
    )
    (net (code "63") (name "unconnected-(J12-SHIELD2-PadS2)") (class "Default")
      (node (ref "J12") (pin "S2") (pinfunction "SHIELD2_S2") (pintype "passive"))
    )
    (net (code "64") (name "unconnected-(U6-EXTCLK-Pad25)") (class "Default")
      (node (ref "U6") (pin "25") (pinfunction "EXTCLK_25") (pintype "passive"))
    )
  )
)
